# J_TAG_SCH.net
KiCad netlist of a schematic drawn in Altium Designer
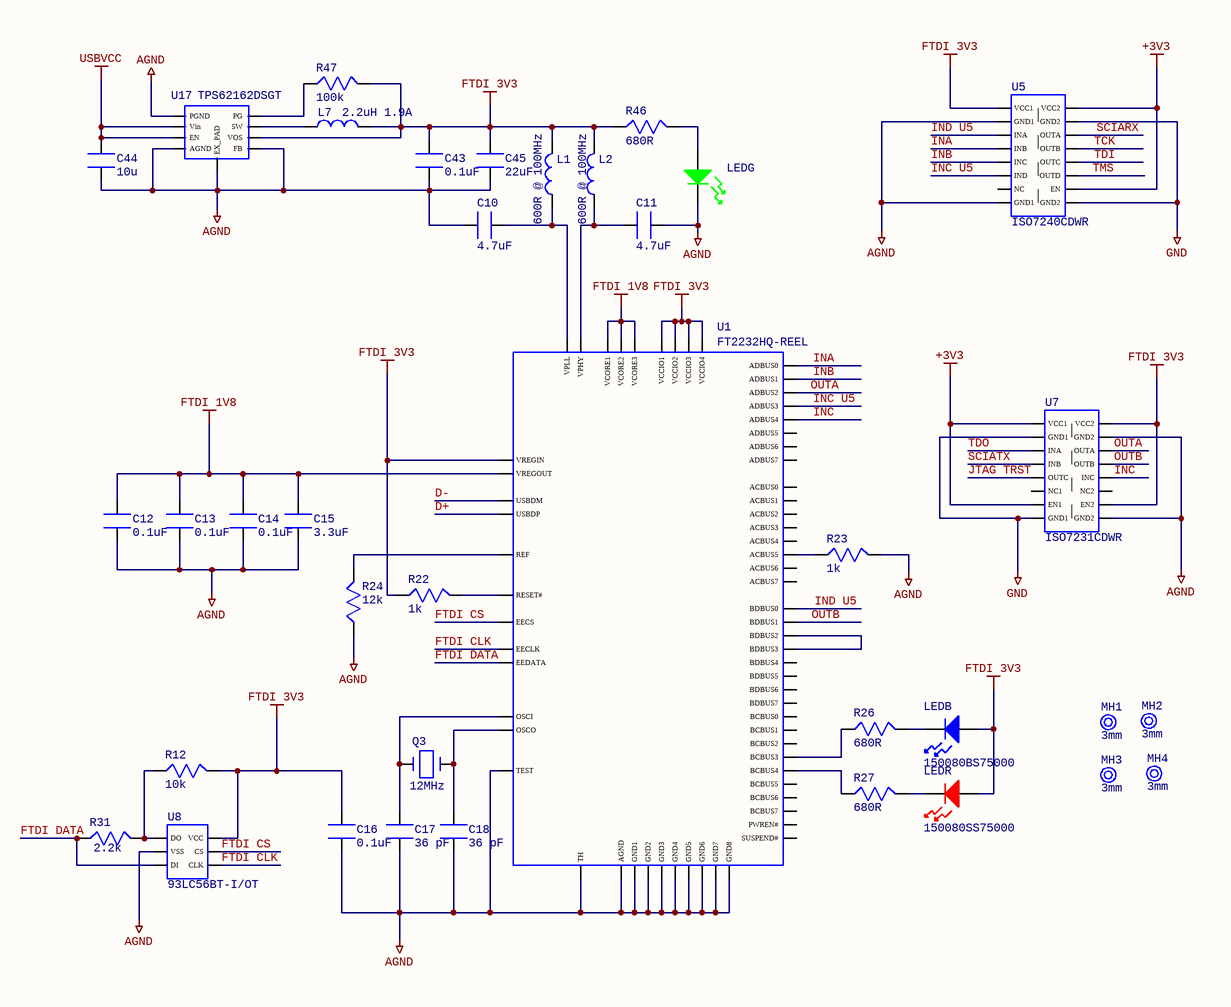
[diagram p0: J_TAG_SCH.SchDoc]

(export (version "E")
  (design (tool "Eeschema 10.0.6"))
  (components
    (comp (ref "C10")
      (value "4.7uF")
      (footprint "GRM155R60J475ME47D")
      (description "C10, C11")
      (libsource (lib "J_Tag") (part "GRM155R60J475ME47D"))
    )
    (comp (ref "C11")
      (value "4.7uF")
      (footprint "GRM155R60J475ME47D")
      (description "C10, C11")
      (libsource (lib "J_Tag") (part "GRM155R60J475ME47D"))
    )
    (comp (ref "C12")
      (value "0.1uF")
      (footprint "GRM155R61A104KA01D")
      (description "C12, C13, C14, C16, C43")
      (libsource (lib "J_Tag") (part "GRM155R61A104KA01D"))
    )
    (comp (ref "C13")
      (value "0.1uF")
      (footprint "GRM155R61A104KA01D")
      (description "C12, C13, C14, C16, C43")
      (libsource (lib "J_Tag") (part "GRM155R61A104KA01D"))
    )
    (comp (ref "C14")
      (value "0.1uF")
      (footprint "GRM155R61A104KA01D")
      (description "C12, C13, C14, C16, C43")
      (libsource (lib "J_Tag") (part "GRM155R61A104KA01D"))
    )
    (comp (ref "C15")
      (value "3.3uF")
      (footprint "C1608X5R1C335K080AC")
      (description "C15")
      (libsource (lib "J_Tag") (part "C1608X5R1C335K080AC"))
    )
    (comp (ref "C16")
      (value "0.1uF")
      (footprint "GRM155R61A104KA01D")
      (description "C12, C13, C14, C16, C43")
      (libsource (lib "J_Tag") (part "GRM155R61A104KA01D"))
    )
    (comp (ref "C17")
      (value "36 pF")
      (footprint "GRM1555C1H360JA01D")
      (description "C17, C18")
      (libsource (lib "J_Tag") (part "GRM1555C1H360JA01D"))
    )
    (comp (ref "C18")
      (value "36 pF")
      (footprint "GRM1555C1H360JA01D")
      (description "C17, C18")
      (libsource (lib "J_Tag") (part "GRM1555C1H360JA01D"))
    )
    (comp (ref "C43")
      (value "0.1uF")
      (footprint "GRM155R61A104KA01D")
      (description "C12, C13, C14, C16, C43")
      (libsource (lib "J_Tag") (part "GRM155R61A104KA01D"))
    )
    (comp (ref "C44")
      (value "10u")
      (footprint "GRM32DR71E106KA12L")
      (description "C41, C44, 10u")
      (libsource (lib "J_Tag") (part "GRM32DR71E106KA12L"))
    )
    (comp (ref "C45")
      (value "22uF")
      (footprint "GRM32ER61E226KE15L")
      (description "C45")
      (libsource (lib "J_Tag") (part "GRM32ER61E226KE15L"))
    )
    (comp (ref "L1")
      (value "600R @ 100MHz")
      (footprint "BLM15AG601SN1D")
      (description "L1, L2")
      (libsource (lib "J_Tag") (part "BLM15AG601SN1D"))
    )
    (comp (ref "L2")
      (value "600R @ 100MHz")
      (footprint "BLM15AG601SN1D")
      (description "L1, L2")
      (libsource (lib "J_Tag") (part "BLM15AG601SN1D"))
    )
    (comp (ref "L7")
      (value "2.2uH 1.9A")
      (footprint "CDRH2D18/HPNP-2R2NC")
      (description "L7")
      (libsource (lib "J_Tag") (part "CDRH2D18/HPNP-2R2NC"))
    )
    (comp (ref "LEDB")
      (value "150080BS75000")
      (footprint "150080BS75000")
      (description "BLUE LED")
      (libsource (lib "J_Tag") (part "150080BS75000onent_1"))
    )
    (comp (ref "LEDG")
      (value "~")
      (footprint "150080VS75000")
      (description "GREEN LED")
      (libsource (lib "J_Tag") (part "150080VS75000"))
    )
    (comp (ref "LEDR")
      (value "150080SS75000")
      (footprint "150080SS75000")
      (description "RED LED")
      (libsource (lib "J_Tag") (part "150080SS75000"))
    )
    (comp (ref "MH1")
      (value "3mm")
      (footprint "MH_3MM")
      (description "odsojnik")
      (libsource (lib "Integrated_Library") (part "TH_3MM"))
    )
    (comp (ref "MH2")
      (value "3mm")
      (footprint "MH_3MM")
      (description "odsojnik")
      (libsource (lib "Integrated_Library") (part "TH_3MM"))
    )
    (comp (ref "MH3")
      (value "3mm")
      (footprint "MH_3MM")
      (description "odsojnik")
      (libsource (lib "Integrated_Library") (part "TH_3MM"))
    )
    (comp (ref "MH4")
      (value "3mm")
      (footprint "MH_3MM")
      (description "odsojnik")
      (libsource (lib "Integrated_Library") (part "TH_3MM"))
    )
    (comp (ref "Q3")
      (value "12MHz")
      (footprint "ABLS2-12.000MHZ-D4Y-T")
      (description "Oscilator 12MHz")
      (libsource (lib "J_Tag") (part "ABLS2-12.000MHZ-D4Y-T"))
    )
    (comp (ref "R12")
      (value "10k")
      (footprint "RC0402FR-0710KL")
      (description "R12, 10K")
      (libsource (lib "J_Tag") (part "RC0402FR-0710KL"))
    )
    (comp (ref "R22")
      (value "1k")
      (footprint "RC0402FR-071KL")
      (description "R22, R23, 1K")
      (libsource (lib "J_Tag") (part "RC0402FR-071KL"))
    )
    (comp (ref "R23")
      (value "1k")
      (footprint "RC0402FR-071KL")
      (description "R22, R23, 1K")
      (libsource (lib "J_Tag") (part "RC0402FR-071KL"))
    )
    (comp (ref "R24")
      (value "12k")
      (footprint "RC0402FR-0712KL")
      (libsource (lib "J_Tag") (part "RC0402FR-0712KL"))
    )
    (comp (ref "R26")
      (value "680R")
      (footprint "RC0402FR-07680RL")
      (description "R26, R27, R46, RC0402FR-07680RL")
      (libsource (lib "J_Tag") (part "RC0402FR-07680RL"))
    )
    (comp (ref "R27")
      (value "680R")
      (footprint "RC0402FR-07680RL")
      (description "R26, R27, R46, RC0402FR-07680RL")
      (libsource (lib "J_Tag") (part "RC0402FR-07680RL"))
    )
    (comp (ref "R31")
      (value "2.2k")
      (footprint "CRCW04022K20FKEDC")
      (description "R31")
      (libsource (lib "J_Tag") (part "CRCW04022K20FKEDC"))
    )
    (comp (ref "R46")
      (value "680R")
      (footprint "RC0402FR-07680RL")
      (description "R26, R27, R46, RC0402FR-07680RL")
      (libsource (lib "J_Tag") (part "RC0402FR-07680RL"))
    )
    (comp (ref "R47")
      (value "100k")
      (footprint "RC0402FR-07100KL")
      (description "100K")
      (libsource (lib "J_Tag") (part "RC0402FR-07100KL"))
    )
    (comp (ref "U1")
      (value "FT2232HQ-REEL")
      (footprint "FT2232HQ-REEL")
      (description "IC kontroler")
      (libsource (lib "J_Tag") (part "FT2232HQ-REEL"))
    )
    (comp (ref "U5")
      (value "ISO7240CDWR")
      (footprint "ISO7240CDWR")
      (description "Izolator")
      (libsource (lib "J_Tag") (part "ISO7240CDWR"))
    )
    (comp (ref "U7")
      (value "ISO7231CDWR")
      (footprint "ISO7231CDWR")
      (description "Izolator")
      (libsource (lib "J_Tag") (part "ISO7231CDWR"))
    )
    (comp (ref "U8")
      (value "93LC56BT-I/OT")
      (footprint "93LC56BT-I/OT")
      (description "IC memorija")
      (libsource (lib "J_Tag") (part "93LC56BT-I/OT"))
    )
    (comp (ref "U17")
      (value "TPS62162DSGT")
      (footprint "TPS62162DSGT")
      (description "DC-DC Buck")
      (libsource (lib "J_Tag") (part "TPS62162DSGT"))
    )
  )
  (nets
    (net (code "1") (name "+3V3") (class "Default")
      (node (ref "U5") (pin "EN") (pinfunction "EN_EN") (pintype "passive"))
      (node (ref "U5") (pin "VCC2") (pinfunction "VCC2_VCC2") (pintype "passive"))
      (node (ref "U7") (pin "EN1") (pinfunction "EN1_EN1") (pintype "passive"))
      (node (ref "U7") (pin "VCC1") (pinfunction "VCC1_VCC1") (pintype "passive"))
    )
    (net (code "2") (name "/D+") (class "Default")
      (node (ref "U1") (pin "USBDP") (pinfunction "USBDP_USBDP") (pintype "passive"))
    )
    (net (code "3") (name "/D-") (class "Default")
      (node (ref "U1") (pin "USBDM") (pinfunction "USBDM_USBDM") (pintype "passive"))
    )
    (net (code "4") (name "/FTDI CLK") (class "Default")
      (node (ref "U1") (pin "EECLK") (pinfunction "EECLK_EECLK") (pintype "passive"))
      (node (ref "U8") (pin "CLK") (pinfunction "CLK_CLK") (pintype "passive"))
    )
    (net (code "5") (name "/FTDI CS") (class "Default")
      (node (ref "U1") (pin "EECS") (pinfunction "EECS_EECS") (pintype "passive"))
      (node (ref "U8") (pin "CS") (pinfunction "CS_CS") (pintype "passive"))
    )
    (net (code "6") (name "/FTDI DATA") (class "Default")
      (node (ref "R31") (pin "1") (pinfunction "1_1") (pintype "passive"))
      (node (ref "U1") (pin "EEDATA") (pinfunction "EEDATA_EEDATA") (pintype "passive"))
      (node (ref "U8") (pin "DI") (pinfunction "DI_DI") (pintype "passive"))
    )
    (net (code "7") (name "/INA") (class "Default")
      (node (ref "U1") (pin "ADBUS0") (pinfunction "ADBUS0_ADBUS0") (pintype "passive"))
      (node (ref "U5") (pin "INB") (pinfunction "INB_INB") (pintype "passive"))
    )
    (net (code "8") (name "/INB") (class "Default")
      (node (ref "U1") (pin "ADBUS1") (pinfunction "ADBUS1_ADBUS1") (pintype "passive"))
      (node (ref "U5") (pin "INC") (pinfunction "INC_INC") (pintype "passive"))
    )
    (net (code "9") (name "/INC") (class "Default")
      (node (ref "U1") (pin "ADBUS4") (pinfunction "ADBUS4_ADBUS4") (pintype "passive"))
      (node (ref "U7") (pin "INC") (pinfunction "INC_INC") (pintype "passive"))
    )
    (net (code "10") (name "/INC U5") (class "Default")
      (node (ref "U1") (pin "ADBUS3") (pinfunction "ADBUS3_ADBUS3") (pintype "passive"))
      (node (ref "U5") (pin "IND") (pinfunction "IND_IND") (pintype "passive"))
    )
    (net (code "11") (name "/IND U5") (class "Default")
      (node (ref "U1") (pin "BDBUS0") (pinfunction "BDBUS0_BDBUS0") (pintype "passive"))
      (node (ref "U5") (pin "INA") (pinfunction "INA_INA") (pintype "passive"))
    )
    (net (code "12") (name "/JTAG TRST") (class "Default")
      (node (ref "U7") (pin "OUTC") (pinfunction "OUTC_OUTC") (pintype "passive"))
    )
    (net (code "13") (name "/OUTA") (class "Default")
      (node (ref "U1") (pin "ADBUS2") (pinfunction "ADBUS2_ADBUS2") (pintype "passive"))
      (node (ref "U7") (pin "OUTA") (pinfunction "OUTA_OUTA") (pintype "passive"))
    )
    (net (code "14") (name "/OUTB") (class "Default")
      (node (ref "U1") (pin "BDBUS1") (pinfunction "BDBUS1_BDBUS1") (pintype "passive"))
      (node (ref "U7") (pin "OUTB") (pinfunction "OUTB_OUTB") (pintype "passive"))
    )
    (net (code "15") (name "/SCIARX") (class "Default")
      (node (ref "U5") (pin "OUTA") (pinfunction "OUTA_OUTA") (pintype "passive"))
    )
    (net (code "16") (name "/SCIATX") (class "Default")
      (node (ref "U7") (pin "INB") (pinfunction "INB_INB") (pintype "passive"))
    )
    (net (code "17") (name "/TCK") (class "Default")
      (node (ref "U5") (pin "OUTB") (pinfunction "OUTB_OUTB") (pintype "passive"))
    )
    (net (code "18") (name "/TDI") (class "Default")
      (node (ref "U5") (pin "OUTC") (pinfunction "OUTC_OUTC") (pintype "passive"))
    )
    (net (code "19") (name "/TDO") (class "Default")
      (node (ref "U7") (pin "INA") (pinfunction "INA_INA") (pintype "passive"))
    )
    (net (code "20") (name "/TMS") (class "Default")
      (node (ref "U5") (pin "OUTD") (pinfunction "OUTD_OUTD") (pintype "passive"))
    )
    (net (code "21") (name "AGND") (class "Default")
      (node (ref "C10") (pin "1") (pinfunction "1_1") (pintype "passive"))
      (node (ref "C11") (pin "2") (pinfunction "2_2") (pintype "passive"))
      (node (ref "C12") (pin "1") (pinfunction "1_1") (pintype "passive"))
      (node (ref "C13") (pin "1") (pinfunction "1_1") (pintype "passive"))
      (node (ref "C14") (pin "1") (pinfunction "1_1") (pintype "passive"))
      (node (ref "C15") (pin "1") (pinfunction "1_1") (pintype "passive"))
      (node (ref "C16") (pin "1") (pinfunction "1_1") (pintype "passive"))
      (node (ref "C17") (pin "1") (pinfunction "1_1") (pintype "passive"))
      (node (ref "C18") (pin "1") (pinfunction "1_1") (pintype "passive"))
      (node (ref "C43") (pin "1") (pinfunction "1_1") (pintype "passive"))
      (node (ref "C44") (pin "1") (pinfunction "1_1") (pintype "passive"))
      (node (ref "C45") (pin "1") (pinfunction "1_1") (pintype "passive"))
      (node (ref "LEDG") (pin "K") (pinfunction "K_K") (pintype "passive"))
      (node (ref "R23") (pin "2") (pinfunction "2_2") (pintype "passive"))
      (node (ref "R24") (pin "1") (pinfunction "1_1") (pintype "passive"))
      (node (ref "U1") (pin "AGND") (pinfunction "AGND_AGND") (pintype "passive"))
      (node (ref "U1") (pin "GND1") (pinfunction "GND1_GND1") (pintype "passive"))
      (node (ref "U1") (pin "GND2") (pinfunction "GND2_GND2") (pintype "passive"))
      (node (ref "U1") (pin "GND3") (pinfunction "GND3_GND3") (pintype "passive"))
      (node (ref "U1") (pin "GND4") (pinfunction "GND4_GND4") (pintype "passive"))
      (node (ref "U1") (pin "GND5") (pinfunction "GND5_GND5") (pintype "passive"))
      (node (ref "U1") (pin "GND6") (pinfunction "GND6_GND6") (pintype "passive"))
      (node (ref "U1") (pin "GND7") (pinfunction "GND7_GND7") (pintype "passive"))
      (node (ref "U1") (pin "GND8") (pinfunction "GND8_GND8") (pintype "passive"))
      (node (ref "U1") (pin "TEST") (pinfunction "TEST_TEST") (pintype "passive"))
      (node (ref "U1") (pin "TH") (pinfunction "TH_TH") (pintype "passive"))
      (node (ref "U17") (pin "AGND") (pinfunction "AGND_AGND") (pintype "passive"))
      (node (ref "U17") (pin "EX_PAD") (pinfunction "EX_PAD_EX_PAD") (pintype "passive"))
      (node (ref "U17") (pin "FB") (pinfunction "FB_FB") (pintype "passive"))
      (node (ref "U17") (pin "PGND") (pinfunction "PGND_PGND") (pintype "passive"))
      (node (ref "U5") (pin "GND1") (pinfunction "GND1_GND1") (pintype "passive"))
      (node (ref "U7") (pin "GND2") (pinfunction "GND2_GND2") (pintype "passive"))
      (node (ref "U8") (pin "VSS") (pinfunction "VSS_VSS") (pintype "passive"))
    )
    (net (code "22") (name "FTDI 1V8") (class "Default")
      (node (ref "C12") (pin "2") (pinfunction "2_2") (pintype "passive"))
      (node (ref "C13") (pin "2") (pinfunction "2_2") (pintype "passive"))
      (node (ref "C14") (pin "2") (pinfunction "2_2") (pintype "passive"))
      (node (ref "C15") (pin "2") (pinfunction "2_2") (pintype "passive"))
      (node (ref "U1") (pin "VCORE1") (pinfunction "VCORE1_VCORE1") (pintype "passive"))
      (node (ref "U1") (pin "VCORE2") (pinfunction "VCORE2_VCORE2") (pintype "passive"))
      (node (ref "U1") (pin "VCORE3") (pinfunction "VCORE3_VCORE3") (pintype "passive"))
      (node (ref "U1") (pin "VREGOUT") (pinfunction "VREGOUT_VREGOUT") (pintype "passive"))
    )
    (net (code "23") (name "FTDI 3V3") (class "Default")
      (node (ref "C16") (pin "2") (pinfunction "2_2") (pintype "passive"))
      (node (ref "C43") (pin "2") (pinfunction "2_2") (pintype "passive"))
      (node (ref "C45") (pin "2") (pinfunction "2_2") (pintype "passive"))
      (node (ref "L1") (pin "1") (pinfunction "1_1") (pintype "passive"))
      (node (ref "L2") (pin "1") (pinfunction "1_1") (pintype "passive"))
      (node (ref "L7") (pin "1") (pinfunction "1_1") (pintype "passive"))
      (node (ref "LEDB") (pin "A") (pinfunction "A_A") (pintype "passive"))
      (node (ref "LEDR") (pin "A") (pinfunction "A_A") (pintype "passive"))
      (node (ref "R12") (pin "2") (pinfunction "2_2") (pintype "passive"))
      (node (ref "R22") (pin "1") (pinfunction "1_1") (pintype "passive"))
      (node (ref "R46") (pin "1") (pinfunction "1_1") (pintype "passive"))
      (node (ref "R47") (pin "2") (pinfunction "2_2") (pintype "passive"))
      (node (ref "U1") (pin "VCCIO1") (pinfunction "VCCIO1_VCCIO1") (pintype "passive"))
      (node (ref "U1") (pin "VCCIO2") (pinfunction "VCCIO2_VCCIO2") (pintype "passive"))
      (node (ref "U1") (pin "VCCIO3") (pinfunction "VCCIO3_VCCIO3") (pintype "passive"))
      (node (ref "U1") (pin "VCCIO4") (pinfunction "VCCIO4_VCCIO4") (pintype "passive"))
      (node (ref "U1") (pin "VREGIN") (pinfunction "VREGIN_VREGIN") (pintype "passive"))
      (node (ref "U17") (pin "VOS") (pinfunction "VOS_VOS") (pintype "passive"))
      (node (ref "U5") (pin "VCC1") (pinfunction "VCC1_VCC1") (pintype "passive"))
      (node (ref "U7") (pin "EN2") (pinfunction "EN2_EN2") (pintype "passive"))
      (node (ref "U7") (pin "VCC2") (pinfunction "VCC2_VCC2") (pintype "passive"))
      (node (ref "U8") (pin "VCC") (pinfunction "VCC_VCC") (pintype "passive"))
    )
    (net (code "24") (name "GND") (class "Default")
      (node (ref "U5") (pin "GND2") (pinfunction "GND2_GND2") (pintype "passive"))
      (node (ref "U7") (pin "GND1") (pinfunction "GND1_GND1") (pintype "passive"))
    )
    (net (code "25") (name "Net-(C10-Pad2)") (class "Default")
      (node (ref "C10") (pin "2") (pinfunction "2_2") (pintype "passive"))
      (node (ref "L1") (pin "2") (pinfunction "2_2") (pintype "passive"))
      (node (ref "U1") (pin "VPLL") (pinfunction "VPLL_VPLL") (pintype "passive"))
    )
    (net (code "26") (name "Net-(C11-Pad1)") (class "Default")
      (node (ref "C11") (pin "1") (pinfunction "1_1") (pintype "passive"))
      (node (ref "L2") (pin "2") (pinfunction "2_2") (pintype "passive"))
      (node (ref "U1") (pin "VPHY") (pinfunction "VPHY_VPHY") (pintype "passive"))
    )
    (net (code "27") (name "Net-(C17-Pad2)") (class "Default")
      (node (ref "C17") (pin "2") (pinfunction "2_2") (pintype "passive"))
      (node (ref "Q3") (pin "1") (pinfunction "1_1") (pintype "passive"))
      (node (ref "U1") (pin "OSCI") (pinfunction "OSCI_OSCI") (pintype "passive"))
    )
    (net (code "28") (name "Net-(C18-Pad2)") (class "Default")
      (node (ref "C18") (pin "2") (pinfunction "2_2") (pintype "passive"))
      (node (ref "Q3") (pin "2") (pinfunction "2_2") (pintype "passive"))
      (node (ref "U1") (pin "OSCO") (pinfunction "OSCO_OSCO") (pintype "passive"))
    )
    (net (code "29") (name "Net-(L7-Pad2)") (class "Default")
      (node (ref "L7") (pin "2") (pinfunction "2_2") (pintype "passive"))
      (node (ref "U17") (pin "SW") (pinfunction "SW_SW") (pintype "passive"))
    )
    (net (code "30") (name "Net-(LEDB-PadK)") (class "Default")
      (node (ref "LEDB") (pin "K") (pinfunction "K_K") (pintype "passive"))
      (node (ref "R26") (pin "2") (pinfunction "2_2") (pintype "passive"))
    )
    (net (code "31") (name "Net-(LEDG-PadA)") (class "Default")
      (node (ref "LEDG") (pin "A") (pinfunction "A_A") (pintype "passive"))
      (node (ref "R46") (pin "2") (pinfunction "2_2") (pintype "passive"))
    )
    (net (code "32") (name "Net-(LEDR-PadK)") (class "Default")
      (node (ref "LEDR") (pin "K") (pinfunction "K_K") (pintype "passive"))
      (node (ref "R27") (pin "2") (pinfunction "2_2") (pintype "passive"))
    )
    (net (code "33") (name "Net-(R12-Pad1)") (class "Default")
      (node (ref "R12") (pin "1") (pinfunction "1_1") (pintype "passive"))
      (node (ref "R31") (pin "2") (pinfunction "2_2") (pintype "passive"))
      (node (ref "U8") (pin "DO") (pinfunction "DO_DO") (pintype "passive"))
    )
    (net (code "34") (name "Net-(R22-Pad2)") (class "Default")
      (node (ref "R22") (pin "2") (pinfunction "2_2") (pintype "passive"))
      (node (ref "U1") (pin "RESET#") (pinfunction "RESET#_RESET#") (pintype "passive"))
    )
    (net (code "35") (name "Net-(R23-Pad1)") (class "Default")
      (node (ref "R23") (pin "1") (pinfunction "1_1") (pintype "passive"))
      (node (ref "U1") (pin "ACBUS5") (pinfunction "ACBUS5_ACBUS5") (pintype "passive"))
    )
    (net (code "36") (name "Net-(R24-Pad2)") (class "Default")
      (node (ref "R24") (pin "2") (pinfunction "2_2") (pintype "passive"))
      (node (ref "U1") (pin "REF") (pinfunction "REF_REF") (pintype "passive"))
    )
    (net (code "37") (name "Net-(R26-Pad1)") (class "Default")
      (node (ref "R26") (pin "1") (pinfunction "1_1") (pintype "passive"))
      (node (ref "U1") (pin "BCBUS3") (pinfunction "BCBUS3_BCBUS3") (pintype "passive"))
    )
    (net (code "38") (name "Net-(R27-Pad1)") (class "Default")
      (node (ref "R27") (pin "1") (pinfunction "1_1") (pintype "passive"))
      (node (ref "U1") (pin "BCBUS4") (pinfunction "BCBUS4_BCBUS4") (pintype "passive"))
    )
    (net (code "39") (name "Net-(R47-Pad1)") (class "Default")
      (node (ref "R47") (pin "1") (pinfunction "1_1") (pintype "passive"))
      (node (ref "U17") (pin "PG") (pinfunction "PG_PG") (pintype "passive"))
    )
    (net (code "40") (name "Net-(U1-PadBDBUS2)") (class "Default")
      (node (ref "U1") (pin "BDBUS2") (pinfunction "BDBUS2_BDBUS2") (pintype "passive"))
      (node (ref "U1") (pin "BDBUS3") (pinfunction "BDBUS3_BDBUS3") (pintype "passive"))
    )
    (net (code "41") (name "USBVCC") (class "Default")
      (node (ref "C44") (pin "2") (pinfunction "2_2") (pintype "passive"))
      (node (ref "U17") (pin "EN") (pinfunction "EN_EN") (pintype "passive"))
      (node (ref "U17") (pin "Vin") (pinfunction "Vin_Vin") (pintype "passive"))
    )
    (net (code "42") (name "unconnected-(U1-PadACBUS0)") (class "Default")
      (node (ref "U1") (pin "ACBUS0") (pinfunction "ACBUS0_ACBUS0") (pintype "passive"))
    )
    (net (code "43") (name "unconnected-(U1-PadACBUS1)") (class "Default")
      (node (ref "U1") (pin "ACBUS1") (pinfunction "ACBUS1_ACBUS1") (pintype "passive"))
    )
    (net (code "44") (name "unconnected-(U1-PadACBUS2)") (class "Default")
      (node (ref "U1") (pin "ACBUS2") (pinfunction "ACBUS2_ACBUS2") (pintype "passive"))
    )
    (net (code "45") (name "unconnected-(U1-PadACBUS3)") (class "Default")
      (node (ref "U1") (pin "ACBUS3") (pinfunction "ACBUS3_ACBUS3") (pintype "passive"))
    )
    (net (code "46") (name "unconnected-(U1-PadACBUS4)") (class "Default")
      (node (ref "U1") (pin "ACBUS4") (pinfunction "ACBUS4_ACBUS4") (pintype "passive"))
    )
    (net (code "47") (name "unconnected-(U1-PadACBUS6)") (class "Default")
      (node (ref "U1") (pin "ACBUS6") (pinfunction "ACBUS6_ACBUS6") (pintype "passive"))
    )
    (net (code "48") (name "unconnected-(U1-PadACBUS7)") (class "Default")
      (node (ref "U1") (pin "ACBUS7") (pinfunction "ACBUS7_ACBUS7") (pintype "passive"))
    )
    (net (code "49") (name "unconnected-(U1-PadADBUS5)") (class "Default")
      (node (ref "U1") (pin "ADBUS5") (pinfunction "ADBUS5_ADBUS5") (pintype "passive"))
    )
    (net (code "50") (name "unconnected-(U1-PadADBUS6)") (class "Default")
      (node (ref "U1") (pin "ADBUS6") (pinfunction "ADBUS6_ADBUS6") (pintype "passive"))
    )
    (net (code "51") (name "unconnected-(U1-PadADBUS7)") (class "Default")
      (node (ref "U1") (pin "ADBUS7") (pinfunction "ADBUS7_ADBUS7") (pintype "passive"))
    )
    (net (code "52") (name "unconnected-(U1-PadBCBUS0)") (class "Default")
      (node (ref "U1") (pin "BCBUS0") (pinfunction "BCBUS0_BCBUS0") (pintype "passive"))
    )
    (net (code "53") (name "unconnected-(U1-PadBCBUS1)") (class "Default")
      (node (ref "U1") (pin "BCBUS1") (pinfunction "BCBUS1_BCBUS1") (pintype "passive"))
    )
    (net (code "54") (name "unconnected-(U1-PadBCBUS2)") (class "Default")
      (node (ref "U1") (pin "BCBUS2") (pinfunction "BCBUS2_BCBUS2") (pintype "passive"))
    )
    (net (code "55") (name "unconnected-(U1-PadBCBUS5)") (class "Default")
      (node (ref "U1") (pin "BCBUS5") (pinfunction "BCBUS5_BCBUS5") (pintype "passive"))
    )
    (net (code "56") (name "unconnected-(U1-PadBCBUS6)") (class "Default")
      (node (ref "U1") (pin "BCBUS6") (pinfunction "BCBUS6_BCBUS6") (pintype "passive"))
    )
    (net (code "57") (name "unconnected-(U1-PadBCBUS7)") (class "Default")
      (node (ref "U1") (pin "BCBUS7") (pinfunction "BCBUS7_BCBUS7") (pintype "passive"))
    )
    (net (code "58") (name "unconnected-(U1-PadBDBUS4)") (class "Default")
      (node (ref "U1") (pin "BDBUS4") (pinfunction "BDBUS4_BDBUS4") (pintype "passive"))
    )
    (net (code "59") (name "unconnected-(U1-PadBDBUS5)") (class "Default")
      (node (ref "U1") (pin "BDBUS5") (pinfunction "BDBUS5_BDBUS5") (pintype "passive"))
    )
    (net (code "60") (name "unconnected-(U1-PadBDBUS6)") (class "Default")
      (node (ref "U1") (pin "BDBUS6") (pinfunction "BDBUS6_BDBUS6") (pintype "passive"))
    )
    (net (code "61") (name "unconnected-(U1-PadBDBUS7)") (class "Default")
      (node (ref "U1") (pin "BDBUS7") (pinfunction "BDBUS7_BDBUS7") (pintype "passive"))
    )
    (net (code "62") (name "unconnected-(U1-PadPWREN#)") (class "Default")
      (node (ref "U1") (pin "PWREN#") (pinfunction "PWREN#_PWREN#") (pintype "passive"))
    )
    (net (code "63") (name "unconnected-(U1-PadSUSPEND#)") (class "Default")
      (node (ref "U1") (pin "SUSPEND#") (pinfunction "SUSPEND#_SUSPEND#") (pintype "passive"))
    )
    (net (code "64") (name "unconnected-(U5-PadNC)") (class "Default")
      (node (ref "U5") (pin "NC") (pinfunction "NC_NC") (pintype "passive"))
    )
    (net (code "65") (name "unconnected-(U7-PadNC1)") (class "Default")
      (node (ref "U7") (pin "NC1") (pinfunction "NC1_NC1") (pintype "passive"))
    )
    (net (code "66") (name "unconnected-(U7-PadNC2)") (class "Default")
      (node (ref "U7") (pin "NC2") (pinfunction "NC2_NC2") (pintype "passive"))
    )
  )
)
